# Sheet1.net
KiCad netlist of a schematic drawn in Altium Designer
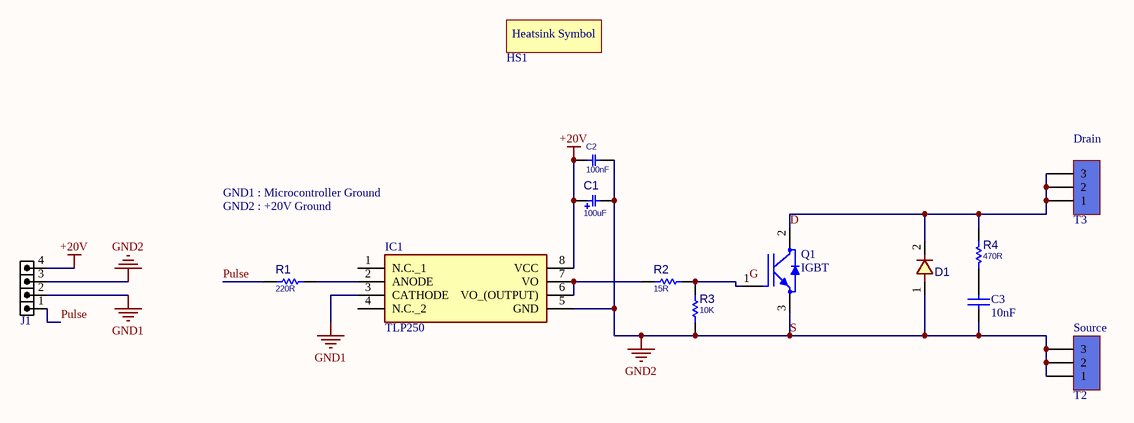
[diagram p0: Sheet1.SchDoc]

(export (version "E")
  (design (tool "Eeschema 10.0.6"))
  (components
    (comp (ref "C1")
      (value "100uF")
      (footprint "C_EL_8X12")
      (description "CAP, THD, ELEC,")
      (fields (field (name "MANF_P#") "MANF_PART#") (field (name "MANF") "MANF"))
      (libsource (lib "passive") (part "CAP_THD_EL"))
    )
    (comp (ref "C2")
      (value "100nF")
      (footprint "C_CER_D3")
      (description "CAP, THD, CER MULTI LAYER,")
      (fields (field (name "MANF_P#") "MANF_PART#") (field (name "MANF") "MANF"))
      (libsource (lib "CapCer_passive") (part "CAP_THD_CERML"))
    )
    (comp (ref "C3")
      (value "10nF")
      (footprint "Cap-10nF-630V")
      (description "CAP Ceramic Total")
      (fields (field (name "DESIGNER") "Ali Hafizi"))
      (libsource (lib "Altium") (part "CAP CERAMIC TOTAL SIZE"))
    )
    (comp (ref "D1")
      (value "1N4007")
      (footprint "D_AX04_DO41")
      (description "DIODE, GENERAL PURPOSE, 1000V/1A")
      (fields (field (name "MANF") "Diodes"))
      (libsource (lib "diode") (part "DIODE_THD_1N4007"))
    )
    (comp (ref "HS1")
      (value "Symbol to use Heatsink on pcb")
      (footprint "HSINK_TO220A")
      (libsource (lib "SidsLIB") (part "Heatsink"))
    )
    (comp (ref "IC1")
      (value "TLP250")
      (footprint "SamacSys:DIP762W50P254L966H445Q8N")
      (description "Integrated Circuit")
      (fields (field (name "RS PART NUMBER") "0768100"))
      (libsource (lib "*") (part "TLP250"))
    )
    (comp (ref "J1")
      (value "HDR1X4")
      (footprint "HDR_M_1X4")
      (description "CONN, HEADER, Male, pitch: 2.54mm, 4POS")
      (libsource (lib "conn_header") (part "HDR_M_1X4"))
    )
    (comp (ref "Q1")
      (value "IGBT")
      (footprint "TO247_3")
      (fields (field (name "MF") "ON Semiconductor") (field (name "MP") "FGH40N60SFDTU"))
      (libsource (lib "SidsLIB") (part "IGBT"))
    )
    (comp (ref "R1")
      (value "220R")
      (footprint "R025W_AX04")
      (description "RESISTOR, THD")
      (fields (field (name "MANF_P#") "RK73H1ETTP4701F") (field (name "MANF") "KOA SPEER"))
      (libsource (lib "passive") (part "RES_THD"))
    )
    (comp (ref "R2")
      (value "15R")
      (footprint "R05W_AX05")
      (description "RESISTOR, THD")
      (fields (field (name "MANF_P#") "RK73H1ETTP4701F") (field (name "MANF") "KOA SPEER"))
      (libsource (lib "passive") (part "RES_THD"))
    )
    (comp (ref "R3")
      (value "10K")
      (footprint "R025W_AX04")
      (description "RESISTOR, THD")
      (fields (field (name "MANF_P#") "RK73H1ETTP4701F") (field (name "MANF") "KOA SPEER"))
      (libsource (lib "passive") (part "RES_THD"))
    )
    (comp (ref "R4")
      (value "470R")
      (footprint "R1W_AX06")
      (description "RESISTOR, THD")
      (fields (field (name "MANF_P#") "RK73H1ETTP4701F") (field (name "MANF") "KOA SPEER"))
      (libsource (lib "passive") (part "RES_THD"))
    )
    (comp (ref "T2")
      (value "KF301_Terminal")
      (footprint "KF301 3PIN")
      (description "Terminal 3 Pin 250VAC 16A")
      (fields (field (name "DESIGNER") "Abbas Basereh"))
      (libsource (lib "Altium") (part "KF301-3Pin_Terminal"))
    )
    (comp (ref "T3")
      (value "KF301_Terminal")
      (footprint "KF301 3PIN")
      (description "Terminal 3 Pin 250VAC 16A")
      (fields (field (name "DESIGNER") "Abbas Basereh"))
      (libsource (lib "Altium") (part "KF301-3Pin_Terminal"))
    )
  )
  (nets
    (net (code "1") (name "+20V") (class "Default")
      (node (ref "C1") (pin "1") (pinfunction "1_1") (pintype "passive"))
      (node (ref "C2") (pin "1") (pinfunction "1_1") (pintype "passive"))
      (node (ref "IC1") (pin "8") (pinfunction "VCC_8") (pintype "passive"))
      (node (ref "J1") (pin "4") (pinfunction "4_4") (pintype "passive"))
    )
    (net (code "2") (name "/D") (class "Default")
      (node (ref "D1") (pin "2") (pinfunction "2_2") (pintype "passive"))
      (node (ref "Q1") (pin "2") (pinfunction "C_2") (pintype "passive"))
      (node (ref "R4") (pin "2") (pinfunction "2_2") (pintype "passive"))
      (node (ref "T3") (pin "1") (pinfunction "1_1") (pintype "passive"))
      (node (ref "T3") (pin "2") (pinfunction "2_2") (pintype "passive"))
      (node (ref "T3") (pin "3") (pinfunction "3_3") (pintype "passive"))
    )
    (net (code "4") (name "/Pulse") (class "Default")
      (node (ref "J1") (pin "1") (pinfunction "1_1") (pintype "passive"))
      (node (ref "R1") (pin "1") (pinfunction "1_1") (pintype "passive"))
    )
    (net (code "5") (name "GND1") (class "Default")
      (node (ref "IC1") (pin "3") (pinfunction "CATHODE_3") (pintype "passive"))
      (node (ref "J1") (pin "2") (pinfunction "2_2") (pintype "passive"))
    )
    (net (code "6") (name "GND2") (class "Default")
      (node (ref "C1") (pin "2") (pinfunction "2_2") (pintype "passive"))
      (node (ref "C2") (pin "2") (pinfunction "2_2") (pintype "passive"))
      (node (ref "C3") (pin "1") (pinfunction "1_1") (pintype "passive"))
      (node (ref "D1") (pin "1") (pinfunction "1_1") (pintype "passive"))
      (node (ref "IC1") (pin "5") (pinfunction "GND_5") (pintype "passive"))
      (node (ref "J1") (pin "3") (pinfunction "3_3") (pintype "passive"))
      (node (ref "Q1") (pin "3") (pinfunction "E_3") (pintype "passive"))
      (node (ref "R3") (pin "1") (pinfunction "1_1") (pintype "passive"))
      (node (ref "T2") (pin "1") (pinfunction "1_1") (pintype "passive"))
      (node (ref "T2") (pin "2") (pinfunction "2_2") (pintype "passive"))
      (node (ref "T2") (pin "3") (pinfunction "3_3") (pintype "passive"))
    )
    (net (code "7") (name "Net-(C3-Pad2)") (class "Default")
      (node (ref "C3") (pin "2") (pinfunction "2_2") (pintype "passive"))
      (node (ref "R4") (pin "1") (pinfunction "1_1") (pintype "passive"))
    )
    (net (code "8") (name "Net-(IC1-ANODE)") (class "Default")
      (node (ref "IC1") (pin "2") (pinfunction "ANODE_2") (pintype "passive"))
      (node (ref "R1") (pin "2") (pinfunction "2_2") (pintype "passive"))
    )
    (net (code "9") (name "Net-(IC1-VO)") (class "Default")
      (node (ref "IC1") (pin "6") (pinfunction "VO_(OUTPUT)_6") (pintype "passive"))
      (node (ref "IC1") (pin "7") (pinfunction "VO_7") (pintype "passive"))
      (node (ref "R2") (pin "1") (pinfunction "1_1") (pintype "passive"))
    )
    (net (code "10") (name "Net-(Q1-G)") (class "Default")
      (node (ref "Q1") (pin "1") (pinfunction "G_1") (pintype "passive"))
      (node (ref "R2") (pin "2") (pinfunction "2_2") (pintype "passive"))
      (node (ref "R3") (pin "2") (pinfunction "2_2") (pintype "passive"))
    )
    (net (code "11") (name "unconnected-(IC1-N.C._1-Pad1)") (class "Default")
      (node (ref "IC1") (pin "1") (pinfunction "N.C._1_1") (pintype "passive"))
    )
    (net (code "12") (name "unconnected-(IC1-N.C._2-Pad4)") (class "Default")
      (node (ref "IC1") (pin "4") (pinfunction "N.C._2_4") (pintype "passive"))
    )
  )
)
